# DIY_OpenEVSE_PLUS_v2w.net
KiCad netlist of a schematic drawn in EAGLE
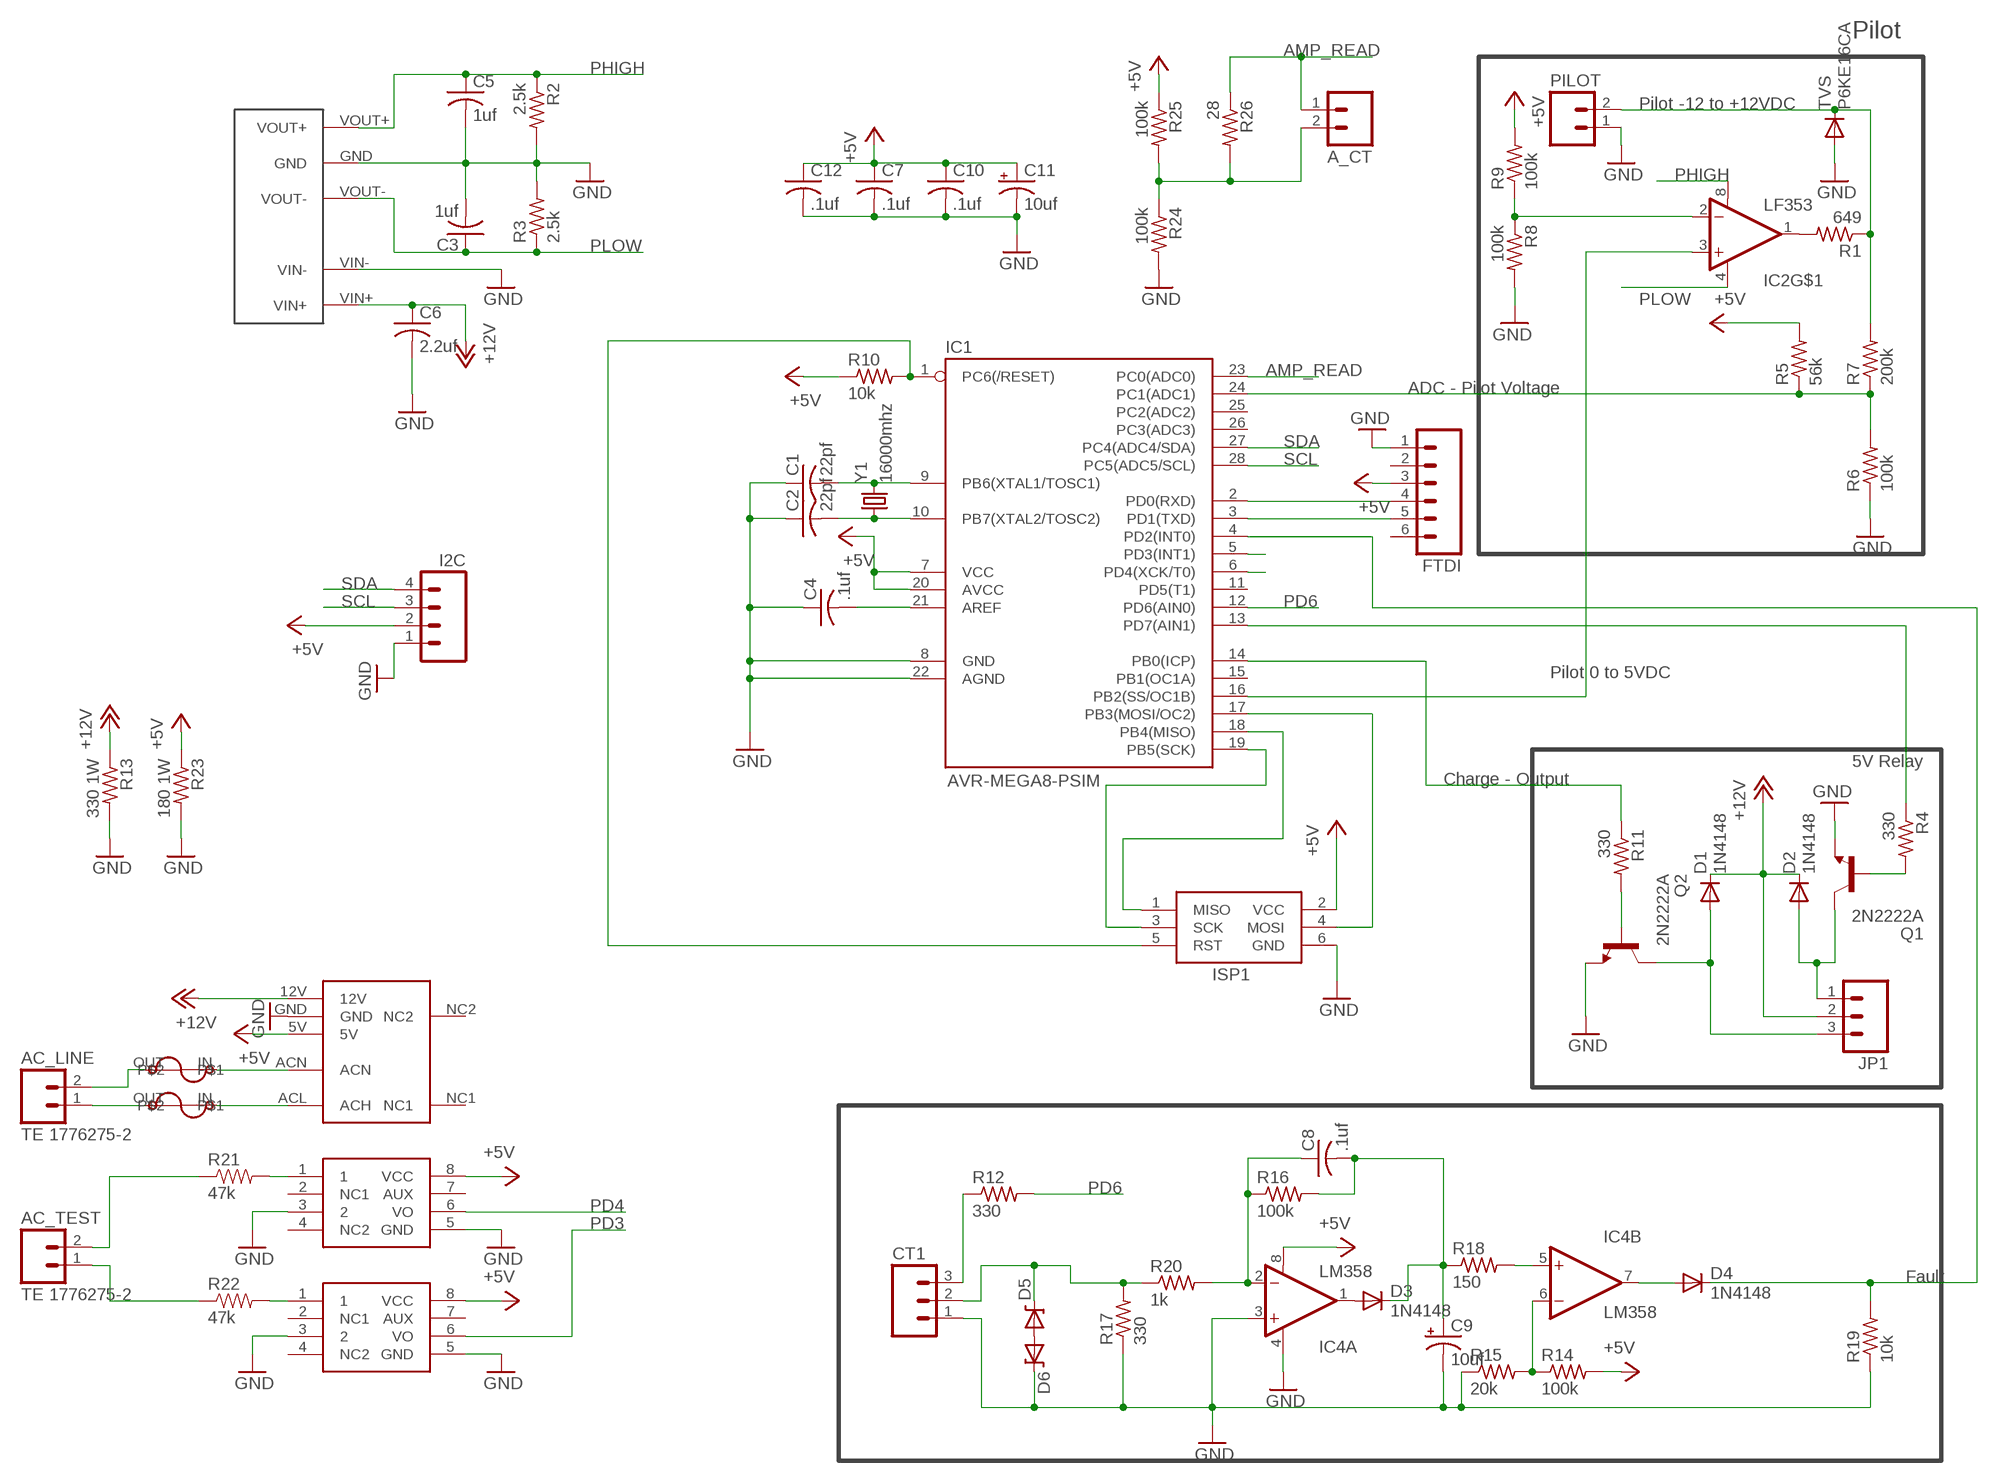
[diagram p0: schematic, sheet 1]

(export (version "E")
  (design (tool "Eeschema 10.0.6"))
  (components
    (comp (ref "AC_LINE")
      (value "TE 1776275-2")
      (footprint "eagle-import:SCREWTERMINAL-3.5MM-2_LOCK")
      (libsource (lib "eagle-import") (part "M023.5MM_LOCK"))
    )
    (comp (ref "AC_TEST")
      (value "TE 1776275-2")
      (footprint "eagle-import:SCREWTERMINAL-3.5MM-2_LOCK")
      (libsource (lib "eagle-import") (part "M023.5MM_LOCK"))
    )
    (comp (ref "A_CT")
      (value "M02PTH")
      (footprint "eagle-import:1X02")
      (libsource (lib "eagle-import") (part "M02PTH"))
    )
    (comp (ref "C1")
      (value "22pf")
      (footprint "eagle-import:C025-024X044")
      (libsource (lib "eagle-import") (part "C-US025-024X044"))
    )
    (comp (ref "C2")
      (value "22pf")
      (footprint "eagle-import:C025-024X044")
      (libsource (lib "eagle-import") (part "C-US025-024X044"))
    )
    (comp (ref "C3")
      (value "1uf")
      (footprint "eagle-import:C025-024X044")
      (libsource (lib "eagle-import") (part "C-US025-024X044"))
    )
    (comp (ref "C4")
      (value ".1uf")
      (footprint "eagle-import:C025-024X044")
      (libsource (lib "eagle-import") (part "C-US025-024X044"))
    )
    (comp (ref "C5")
      (value "1uf")
      (footprint "eagle-import:C025-024X044")
      (libsource (lib "eagle-import") (part "C-US025-024X044"))
    )
    (comp (ref "C6")
      (value "2.2uf")
      (footprint "eagle-import:C025-024X044")
      (libsource (lib "eagle-import") (part "C-US025-024X044"))
    )
    (comp (ref "C7")
      (value ".1uf")
      (footprint "eagle-import:C025-024X044")
      (libsource (lib "eagle-import") (part "C-US025-024X044"))
    )
    (comp (ref "C8")
      (value ".1uf")
      (footprint "eagle-import:C025-024X044")
      (libsource (lib "eagle-import") (part "C-US025-024X044"))
    )
    (comp (ref "C9")
      (value "10uf")
      (footprint "eagle-import:CPOL-RADIAL-10UF-25V")
      (libsource (lib "eagle-import") (part "CAP_POLPTH2"))
    )
    (comp (ref "C10")
      (value ".1uf")
      (footprint "eagle-import:C025-024X044")
      (libsource (lib "eagle-import") (part "C-US025-024X044"))
    )
    (comp (ref "C11")
      (value "10uf")
      (footprint "eagle-import:CPOL-RADIAL-10UF-25V")
      (libsource (lib "eagle-import") (part "CAP_POLPTH2"))
    )
    (comp (ref "C12")
      (value ".1uf")
      (footprint "eagle-import:C025-024X044")
      (libsource (lib "eagle-import") (part "C-US025-024X044"))
    )
    (comp (ref "CT1")
      (value "M03LOCK")
      (footprint "eagle-import:1X03_LOCK")
      (libsource (lib "eagle-import") (part "M03LOCK"))
    )
    (comp (ref "D1")
      (value "1N4148")
      (footprint "eagle-import:DIODE-1N4148")
      (libsource (lib "eagle-import") (part "DIODE1N4148"))
    )
    (comp (ref "D2")
      (value "1N4148")
      (footprint "eagle-import:DIODE-1N4148")
      (libsource (lib "eagle-import") (part "DIODE1N4148"))
    )
    (comp (ref "D3")
      (value "1N4148")
      (footprint "eagle-import:DIODE-1N4148")
      (libsource (lib "eagle-import") (part "DIODE1N4148"))
    )
    (comp (ref "D4")
      (value "1N4148")
      (footprint "eagle-import:DIODE-1N4148")
      (libsource (lib "eagle-import") (part "DIODE1N4148"))
    )
    (comp (ref "D5")
      (value "DIODE-ZENERPTH")
      (footprint "eagle-import:DIODE-ZENER")
      (libsource (lib "eagle-import") (part "DIODE-ZENERPTH"))
    )
    (comp (ref "D6")
      (value "DIODE-ZENERPTH")
      (footprint "eagle-import:DIODE-ZENER")
      (libsource (lib "eagle-import") (part "DIODE-ZENERPTH"))
    )
    (comp (ref "DCDC")
      (value "D107E")
      (footprint "eagle-import:DCDC_SIP")
      (libsource (lib "eagle-import") (part "DCDC_SIP"))
    )
    (comp (ref "FTDI")
      (value "M06LOCK")
      (footprint "eagle-import:1X06_LOCK")
      (libsource (lib "eagle-import") (part "M06LOCK"))
    )
    (comp (ref "I2C")
      (value "M04LOCK")
      (footprint "eagle-import:1X04_LOCK")
      (libsource (lib "eagle-import") (part "M04LOCK"))
    )
    (comp (ref "IC1")
      (value "AVR-MEGA8-PSIM")
      (footprint "eagle-import:DIL28-3-SIMON")
      (libsource (lib "eagle-import") (part "AVR-MEGA8-PSIM"))
    )
    (comp (ref "IC2")
      (value "LF353")
      (footprint "eagle-import:DIP08")
      (libsource (lib "eagle-import") (part "LM358"))
    )
    (comp (ref "IC3")
      (value "MID400")
      (footprint "eagle-import:DIP08")
      (libsource (lib "eagle-import") (part "MID400"))
    )
    (comp (ref "IC4")
      (value "LM358")
      (footprint "eagle-import:DIP08")
      (libsource (lib "eagle-import") (part "OPAMP-DUALDIP"))
    )
    (comp (ref "IC5")
      (value "MID400")
      (footprint "eagle-import:DIP08")
      (libsource (lib "eagle-import") (part "MID400"))
    )
    (comp (ref "ISP1")
      (value "AVRISP-6")
      (footprint "eagle-import:AVRISP")
      (libsource (lib "eagle-import") (part "AVRISP-6"))
    )
    (comp (ref "JP1")
      (value "M03SCREW_LOCK")
      (footprint "eagle-import:SCREWTERMINAL-3.5MM-3_LOCK.007S")
      (libsource (lib "eagle-import") (part "M03SCREW_LOCK"))
    )
    (comp (ref "PILOT")
      (value "M025MM")
      (footprint "eagle-import:SCREWTERMINAL-5MM-2")
      (libsource (lib "eagle-import") (part "M025MM"))
    )
    (comp (ref "Q1")
      (value "2N2222A")
      (footprint "eagle-import:TO18")
      (libsource (lib "eagle-import") (part "2N2222A"))
    )
    (comp (ref "Q2")
      (value "2N2222A")
      (footprint "eagle-import:TO18")
      (libsource (lib "eagle-import") (part "2N2222A"))
    )
    (comp (ref "R1")
      (value "649")
      (footprint "eagle-import:0309V")
      (libsource (lib "eagle-import") (part "R-US_0309/V"))
    )
    (comp (ref "R2")
      (value "2.5k")
      (footprint "eagle-import:0309V")
      (libsource (lib "eagle-import") (part "R-US_0309/V"))
    )
    (comp (ref "R3")
      (value "2.5k")
      (footprint "eagle-import:0309V")
      (libsource (lib "eagle-import") (part "R-US_0309/V"))
    )
    (comp (ref "R4")
      (value "330")
      (footprint "eagle-import:0309V")
      (libsource (lib "eagle-import") (part "R-US_0309/V"))
    )
    (comp (ref "R5")
      (value "56k")
      (footprint "eagle-import:0309V")
      (libsource (lib "eagle-import") (part "R-US_0309/V"))
    )
    (comp (ref "R6")
      (value "100k")
      (footprint "eagle-import:0309V")
      (libsource (lib "eagle-import") (part "R-US_0309/V"))
    )
    (comp (ref "R7")
      (value "200k")
      (footprint "eagle-import:0309V")
      (libsource (lib "eagle-import") (part "R-US_0309/V"))
    )
    (comp (ref "R8")
      (value "100k")
      (footprint "eagle-import:0309V")
      (libsource (lib "eagle-import") (part "R-US_0309/V"))
    )
    (comp (ref "R9")
      (value "100k")
      (footprint "eagle-import:0309V")
      (libsource (lib "eagle-import") (part "R-US_0309/V"))
    )
    (comp (ref "R10")
      (value "10k")
      (footprint "eagle-import:0309V")
      (libsource (lib "eagle-import") (part "R-US_0309/V"))
    )
    (comp (ref "R11")
      (value "330")
      (footprint "eagle-import:0309V")
      (libsource (lib "eagle-import") (part "R-US_0309/V"))
    )
    (comp (ref "R12")
      (value "330")
      (footprint "eagle-import:0309V")
      (libsource (lib "eagle-import") (part "R-US_0309/V"))
    )
    (comp (ref "R13")
      (value "330 1W")
      (footprint "eagle-import:0309V")
      (libsource (lib "eagle-import") (part "R-US_0309/V"))
    )
    (comp (ref "R14")
      (value "100k")
      (footprint "eagle-import:0309V")
      (libsource (lib "eagle-import") (part "R-US_0309/V"))
    )
    (comp (ref "R15")
      (value "20k")
      (footprint "eagle-import:0309V")
      (libsource (lib "eagle-import") (part "R-US_0309/V"))
    )
    (comp (ref "R16")
      (value "100k")
      (footprint "eagle-import:0309V")
      (libsource (lib "eagle-import") (part "R-US_0309/V"))
    )
    (comp (ref "R17")
      (value "330")
      (footprint "eagle-import:0309V")
      (libsource (lib "eagle-import") (part "R-US_0309/V"))
    )
    (comp (ref "R18")
      (value "150")
      (footprint "eagle-import:0309V")
      (libsource (lib "eagle-import") (part "R-US_0309/V"))
    )
    (comp (ref "R19")
      (value "10k")
      (footprint "eagle-import:0309V")
      (libsource (lib "eagle-import") (part "R-US_0309/V"))
    )
    (comp (ref "R20")
      (value "1k")
      (footprint "eagle-import:0309V")
      (libsource (lib "eagle-import") (part "R-US_0309/V"))
    )
    (comp (ref "R21")
      (value "47k")
      (footprint "eagle-import:AXIAL-0.4")
      (libsource (lib "eagle-import") (part "RESISTORPTH-1/4W"))
    )
    (comp (ref "R22")
      (value "47k")
      (footprint "eagle-import:AXIAL-0.4")
      (libsource (lib "eagle-import") (part "RESISTORPTH-1/4W"))
    )
    (comp (ref "R23")
      (value "180 1W")
      (footprint "eagle-import:0309V")
      (libsource (lib "eagle-import") (part "R-US_0309/V"))
    )
    (comp (ref "R24")
      (value "100k")
      (footprint "eagle-import:0309V")
      (libsource (lib "eagle-import") (part "rcl_R-US_0309/V"))
    )
    (comp (ref "R25")
      (value "100k")
      (footprint "eagle-import:0309V")
      (libsource (lib "eagle-import") (part "rcl_R-US_0309/V"))
    )
    (comp (ref "R26")
      (value "28")
      (footprint "eagle-import:0309V")
      (libsource (lib "eagle-import") (part "rcl_R-US_0309/V"))
    )
    (comp (ref "TVS")
      (value "P6KE16CA")
      (footprint "eagle-import:DIODE-1N4001")
      (libsource (lib "eagle-import") (part "DIODEPTH"))
    )
    (comp (ref "U$3")
      (value "BEL1AFUSE")
      (footprint "eagle-import:BELFUSE1A")
      (libsource (lib "eagle-import") (part "BEL1AFUSE"))
    )
    (comp (ref "U$4")
      (value "MPM-04E-1205")
      (footprint "eagle-import:MPM-04E-1205")
      (libsource (lib "eagle-import") (part "MPM-04E-1205"))
    )
    (comp (ref "U$5")
      (value "BEL1AFUSE")
      (footprint "eagle-import:BELFUSE1A")
      (libsource (lib "eagle-import") (part "BEL1AFUSE"))
    )
    (comp (ref "Y1")
      (value "16000mhz")
      (footprint "eagle-import:HC49U-V")
      (libsource (lib "eagle-import") (part "CRYSTALHC49UV"))
    )
  )
  (nets
    (net (code "1") (name "+5V") (class "Default")
      (node (ref "C10") (pin "1") (pinfunction "1_1") (pintype "passive"))
      (node (ref "C11") (pin "1") (pinfunction "+_1") (pintype "passive"))
      (node (ref "C12") (pin "1") (pinfunction "1_1") (pintype "passive"))
      (node (ref "C7") (pin "1") (pinfunction "1_1") (pintype "passive"))
      (node (ref "FTDI") (pin "3") (pinfunction "3_3") (pintype "passive"))
      (node (ref "I2C") (pin "2") (pinfunction "2_2") (pintype "passive"))
      (node (ref "IC1") (pin "20") (pinfunction "AVCC_20") (pintype "bidirectional"))
      (node (ref "IC1") (pin "7") (pinfunction "VCC_7") (pintype "bidirectional"))
      (node (ref "IC3") (pin "8") (pinfunction "VCC_8") (pintype "bidirectional"))
      (node (ref "IC4") (pin "8") (pinfunction "V+_8") (pintype "power_in"))
      (node (ref "IC5") (pin "8") (pinfunction "VCC_8") (pintype "bidirectional"))
      (node (ref "ISP1") (pin "2") (pinfunction "VCC_2") (pintype "power_in"))
      (node (ref "R10") (pin "1") (pinfunction "1_1") (pintype "passive"))
      (node (ref "R14") (pin "2") (pinfunction "2_2") (pintype "passive"))
      (node (ref "R23") (pin "1") (pinfunction "1_1") (pintype "passive"))
      (node (ref "R25") (pin "1") (pinfunction "1_1") (pintype "passive"))
      (node (ref "R5") (pin "2") (pinfunction "2_2") (pintype "passive"))
      (node (ref "R9") (pin "2") (pinfunction "2_2") (pintype "passive"))
      (node (ref "U$4") (pin "5V") (pinfunction "5V_5V") (pintype "bidirectional"))
    )
    (net (code "2") (name "+12V") (class "Default")
      (node (ref "C6") (pin "1") (pinfunction "1_1") (pintype "passive"))
      (node (ref "D1") (pin "C") (pinfunction "C_C") (pintype "passive"))
      (node (ref "D2") (pin "C") (pinfunction "C_C") (pintype "passive"))
      (node (ref "DCDC") (pin "VIN+") (pinfunction "VIN+_VIN+") (pintype "bidirectional"))
      (node (ref "JP1") (pin "2") (pinfunction "2_2") (pintype "passive"))
      (node (ref "R13") (pin "1") (pinfunction "1_1") (pintype "passive"))
      (node (ref "U$4") (pin "12V") (pinfunction "12V_12V") (pintype "bidirectional"))
    )
    (net (code "3") (name "/AMP_READ") (class "Default")
      (node (ref "A_CT") (pin "1") (pinfunction "1_1") (pintype "passive"))
      (node (ref "IC1") (pin "23") (pinfunction "PC0(ADC0)_23") (pintype "bidirectional"))
      (node (ref "R26") (pin "1") (pinfunction "1_1") (pintype "passive"))
    )
    (net (code "4") (name "/PD3") (class "Default")
      (node (ref "IC1") (pin "5") (pinfunction "PD3(INT1)_5") (pintype "bidirectional"))
      (node (ref "IC5") (pin "6") (pinfunction "VO_6") (pintype "bidirectional"))
    )
    (net (code "5") (name "/PD4") (class "Default")
      (node (ref "IC1") (pin "6") (pinfunction "PD4(XCK/T0)_6") (pintype "bidirectional"))
      (node (ref "IC3") (pin "6") (pinfunction "VO_6") (pintype "bidirectional"))
    )
    (net (code "6") (name "/PD6") (class "Default")
      (node (ref "IC1") (pin "12") (pinfunction "PD6(AIN0)_12") (pintype "bidirectional"))
      (node (ref "R12") (pin "2") (pinfunction "2_2") (pintype "passive"))
    )
    (net (code "7") (name "/PHIGH") (class "Default")
      (node (ref "C5") (pin "1") (pinfunction "1_1") (pintype "passive"))
      (node (ref "DCDC") (pin "VOUT+") (pinfunction "VOUT+_VOUT+") (pintype "bidirectional"))
      (node (ref "IC2") (pin "8") (pinfunction "V+_8") (pintype "power_in"))
      (node (ref "R2") (pin "1") (pinfunction "1_1") (pintype "passive"))
    )
    (net (code "8") (name "/PLOW") (class "Default")
      (node (ref "C3") (pin "1") (pinfunction "1_1") (pintype "passive"))
      (node (ref "DCDC") (pin "VOUT-") (pinfunction "VOUT-_VOUT-") (pintype "bidirectional"))
      (node (ref "IC2") (pin "4") (pinfunction "V-_4") (pintype "power_in"))
      (node (ref "R3") (pin "1") (pinfunction "1_1") (pintype "passive"))
    )
    (net (code "9") (name "/SCL") (class "Default")
      (node (ref "I2C") (pin "3") (pinfunction "3_3") (pintype "passive"))
      (node (ref "IC1") (pin "28") (pinfunction "PC5(ADC5/SCL)_28") (pintype "bidirectional"))
    )
    (net (code "10") (name "/SDA") (class "Default")
      (node (ref "I2C") (pin "4") (pinfunction "4_4") (pintype "passive"))
      (node (ref "IC1") (pin "27") (pinfunction "PC4(ADC4/SDA)_27") (pintype "bidirectional"))
    )
    (net (code "11") (name "GND") (class "Default")
      (node (ref "C1") (pin "1") (pinfunction "1_1") (pintype "passive"))
      (node (ref "C10") (pin "2") (pinfunction "2_2") (pintype "passive"))
      (node (ref "C11") (pin "2") (pinfunction "-_2") (pintype "passive"))
      (node (ref "C12") (pin "2") (pinfunction "2_2") (pintype "passive"))
      (node (ref "C2") (pin "1") (pinfunction "1_1") (pintype "passive"))
      (node (ref "C3") (pin "2") (pinfunction "2_2") (pintype "passive"))
      (node (ref "C4") (pin "1") (pinfunction "1_1") (pintype "passive"))
      (node (ref "C5") (pin "2") (pinfunction "2_2") (pintype "passive"))
      (node (ref "C6") (pin "2") (pinfunction "2_2") (pintype "passive"))
      (node (ref "C7") (pin "2") (pinfunction "2_2") (pintype "passive"))
      (node (ref "C9") (pin "2") (pinfunction "-_2") (pintype "passive"))
      (node (ref "CT1") (pin "1") (pinfunction "1_1") (pintype "passive"))
      (node (ref "D6") (pin "P$1") (pinfunction "C_P$1") (pintype "passive"))
      (node (ref "DCDC") (pin "GND") (pinfunction "GND_GND") (pintype "bidirectional"))
      (node (ref "DCDC") (pin "VIN-") (pinfunction "VIN-_VIN-") (pintype "bidirectional"))
      (node (ref "FTDI") (pin "1") (pinfunction "1_1") (pintype "passive"))
      (node (ref "I2C") (pin "1") (pinfunction "1_1") (pintype "passive"))
      (node (ref "IC1") (pin "22") (pinfunction "AGND_22") (pintype "bidirectional"))
      (node (ref "IC1") (pin "8") (pinfunction "GND_8") (pintype "bidirectional"))
      (node (ref "IC3") (pin "3") (pinfunction "2_3") (pintype "bidirectional"))
      (node (ref "IC3") (pin "5") (pinfunction "GND_5") (pintype "bidirectional"))
      (node (ref "IC4") (pin "3") (pinfunction "+IN_3") (pintype "input"))
      (node (ref "IC4") (pin "4") (pinfunction "V-_4") (pintype "power_in"))
      (node (ref "IC5") (pin "3") (pinfunction "2_3") (pintype "bidirectional"))
      (node (ref "IC5") (pin "5") (pinfunction "GND_5") (pintype "bidirectional"))
      (node (ref "ISP1") (pin "6") (pinfunction "GND_6") (pintype "power_in"))
      (node (ref "PILOT") (pin "1") (pinfunction "1_1") (pintype "passive"))
      (node (ref "Q1") (pin "1") (pinfunction "E_1") (pintype "passive"))
      (node (ref "Q2") (pin "1") (pinfunction "E_1") (pintype "passive"))
      (node (ref "R13") (pin "2") (pinfunction "2_2") (pintype "passive"))
      (node (ref "R15") (pin "1") (pinfunction "1_1") (pintype "passive"))
      (node (ref "R17") (pin "1") (pinfunction "1_1") (pintype "passive"))
      (node (ref "R19") (pin "1") (pinfunction "1_1") (pintype "passive"))
      (node (ref "R2") (pin "2") (pinfunction "2_2") (pintype "passive"))
      (node (ref "R23") (pin "2") (pinfunction "2_2") (pintype "passive"))
      (node (ref "R24") (pin "2") (pinfunction "2_2") (pintype "passive"))
      (node (ref "R3") (pin "2") (pinfunction "2_2") (pintype "passive"))
      (node (ref "R6") (pin "1") (pinfunction "1_1") (pintype "passive"))
      (node (ref "R8") (pin "2") (pinfunction "2_2") (pintype "passive"))
      (node (ref "TVS") (pin "A") (pinfunction "A_A") (pintype "passive"))
      (node (ref "U$4") (pin "GND") (pinfunction "GND_GND") (pintype "bidirectional"))
    )
    (net (code "12") (name "Net-(A_CT-Pad2)") (class "Default")
      (node (ref "A_CT") (pin "2") (pinfunction "2_2") (pintype "passive"))
      (node (ref "R24") (pin "1") (pinfunction "1_1") (pintype "passive"))
      (node (ref "R25") (pin "2") (pinfunction "2_2") (pintype "passive"))
      (node (ref "R26") (pin "2") (pinfunction "2_2") (pintype "passive"))
    )
    (net (code "13") (name "Net-(C9-+)") (class "Default")
      (node (ref "C8") (pin "2") (pinfunction "2_2") (pintype "passive"))
      (node (ref "C9") (pin "1") (pinfunction "+_1") (pintype "passive"))
      (node (ref "D3") (pin "C") (pinfunction "C_C") (pintype "passive"))
      (node (ref "R16") (pin "2") (pinfunction "2_2") (pintype "passive"))
      (node (ref "R18") (pin "1") (pinfunction "1_1") (pintype "passive"))
    )
    (net (code "14") (name "Net-(CT1-Pad3)") (class "Default")
      (node (ref "CT1") (pin "3") (pinfunction "3_3") (pintype "passive"))
      (node (ref "R12") (pin "1") (pinfunction "1_1") (pintype "passive"))
    )
    (net (code "15") (name "Net-(D5-A)") (class "Default")
      (node (ref "D5") (pin "P$2") (pinfunction "A_P$2") (pintype "passive"))
      (node (ref "D6") (pin "P$2") (pinfunction "A_P$2") (pintype "passive"))
    )
    (net (code "16") (name "Net-(D5-C)") (class "Default")
      (node (ref "CT1") (pin "2") (pinfunction "2_2") (pintype "passive"))
      (node (ref "D5") (pin "P$1") (pinfunction "C_P$1") (pintype "passive"))
      (node (ref "R17") (pin "2") (pinfunction "2_2") (pintype "passive"))
      (node (ref "R20") (pin "1") (pinfunction "1_1") (pintype "passive"))
    )
    (net (code "17") (name "Net-(IC1-AREF)") (class "Default")
      (node (ref "C4") (pin "2") (pinfunction "2_2") (pintype "passive"))
      (node (ref "IC1") (pin "21") (pinfunction "AREF_21") (pintype "bidirectional"))
    )
    (net (code "18") (name "Net-(IC1-PB0(ICP))") (class "Default")
      (node (ref "IC1") (pin "14") (pinfunction "PB0(ICP)_14") (pintype "bidirectional"))
      (node (ref "R11") (pin "1") (pinfunction "1_1") (pintype "passive"))
    )
    (net (code "19") (name "Net-(IC1-PB2(SS{slash}OC1B))") (class "Default")
      (node (ref "IC1") (pin "16") (pinfunction "PB2(SS/OC1B)_16") (pintype "bidirectional"))
      (node (ref "IC2") (pin "3") (pinfunction "+IN_3") (pintype "input"))
    )
    (net (code "20") (name "Net-(IC1-PB3(MOSI{slash}OC2))") (class "Default")
      (node (ref "IC1") (pin "17") (pinfunction "PB3(MOSI/OC2)_17") (pintype "bidirectional"))
      (node (ref "ISP1") (pin "4") (pinfunction "MOSI_4") (pintype "output"))
    )
    (net (code "21") (name "Net-(IC1-PB4(MISO))") (class "Default")
      (node (ref "IC1") (pin "18") (pinfunction "PB4(MISO)_18") (pintype "bidirectional"))
      (node (ref "ISP1") (pin "1") (pinfunction "MISO_1") (pintype "input"))
    )
    (net (code "22") (name "Net-(IC1-PB5(SCK))") (class "Default")
      (node (ref "IC1") (pin "19") (pinfunction "PB5(SCK)_19") (pintype "bidirectional"))
      (node (ref "ISP1") (pin "3") (pinfunction "SCK_3") (pintype "output"))
    )
    (net (code "23") (name "Net-(IC1-PB6(XTAL1{slash}TOSC1))") (class "Default")
      (node (ref "C1") (pin "2") (pinfunction "2_2") (pintype "passive"))
      (node (ref "IC1") (pin "9") (pinfunction "PB6(XTAL1/TOSC1)_9") (pintype "bidirectional"))
      (node (ref "Y1") (pin "2") (pinfunction "2_2") (pintype "passive"))
    )
    (net (code "24") (name "Net-(IC1-PB7(XTAL2{slash}TOSC2))") (class "Default")
      (node (ref "C2") (pin "2") (pinfunction "2_2") (pintype "passive"))
      (node (ref "IC1") (pin "10") (pinfunction "PB7(XTAL2/TOSC2)_10") (pintype "bidirectional"))
      (node (ref "Y1") (pin "1") (pinfunction "1_1") (pintype "passive"))
    )
    (net (code "25") (name "Net-(IC1-PC1(ADC1))") (class "Default")
      (node (ref "IC1") (pin "24") (pinfunction "PC1(ADC1)_24") (pintype "bidirectional"))
      (node (ref "R5") (pin "1") (pinfunction "1_1") (pintype "passive"))
      (node (ref "R6") (pin "2") (pinfunction "2_2") (pintype "passive"))
      (node (ref "R7") (pin "1") (pinfunction "1_1") (pintype "passive"))
    )
    (net (code "26") (name "Net-(IC1-PC6({slash}RESET))") (class "Default")
      (node (ref "IC1") (pin "1") (pinfunction "PC6(/RESET)_1") (pintype "bidirectional"))
      (node (ref "ISP1") (pin "5") (pinfunction "RST_5") (pintype "output"))
      (node (ref "R10") (pin "2") (pinfunction "2_2") (pintype "passive"))
    )
    (net (code "27") (name "Net-(IC1-PD0(RXD))") (class "Default")
      (node (ref "FTDI") (pin "4") (pinfunction "4_4") (pintype "passive"))
      (node (ref "IC1") (pin "2") (pinfunction "PD0(RXD)_2") (pintype "bidirectional"))
    )
    (net (code "28") (name "Net-(IC1-PD1(TXD))") (class "Default")
      (node (ref "FTDI") (pin "5") (pinfunction "5_5") (pintype "passive"))
      (node (ref "IC1") (pin "3") (pinfunction "PD1(TXD)_3") (pintype "bidirectional"))
    )
    (net (code "29") (name "Net-(IC1-PD2(INT0))") (class "Default")
      (node (ref "D4") (pin "C") (pinfunction "C_C") (pintype "passive"))
      (node (ref "IC1") (pin "4") (pinfunction "PD2(INT0)_4") (pintype "bidirectional"))
      (node (ref "R19") (pin "2") (pinfunction "2_2") (pintype "passive"))
    )
    (net (code "30") (name "Net-(IC1-PD7(AIN1))") (class "Default")
      (node (ref "IC1") (pin "13") (pinfunction "PD7(AIN1)_13") (pintype "bidirectional"))
      (node (ref "R4") (pin "1") (pinfunction "1_1") (pintype "passive"))
    )
    (net (code "31") (name "Net-(IC2A--IN)") (class "Default")
      (node (ref "IC2") (pin "2") (pinfunction "-IN_2") (pintype "input"))
      (node (ref "R8") (pin "1") (pinfunction "1_1") (pintype "passive"))
      (node (ref "R9") (pin "1") (pinfunction "1_1") (pintype "passive"))
    )
    (net (code "32") (name "Net-(IC2A-OUT)") (class "Default")
      (node (ref "IC2") (pin "1") (pinfunction "OUT_1") (pintype "output"))
      (node (ref "R1") (pin "2") (pinfunction "2_2") (pintype "passive"))
    )
    (net (code "33") (name "Net-(IC4A--IN)") (class "Default")
      (node (ref "C8") (pin "1") (pinfunction "1_1") (pintype "passive"))
      (node (ref "IC4") (pin "2") (pinfunction "-IN_2") (pintype "input"))
      (node (ref "R16") (pin "1") (pinfunction "1_1") (pintype "passive"))
      (node (ref "R20") (pin "2") (pinfunction "2_2") (pintype "passive"))
    )
    (net (code "34") (name "Net-(IC4A-OUT)") (class "Default")
      (node (ref "D3") (pin "A") (pinfunction "A_A") (pintype "passive"))
      (node (ref "IC4") (pin "1") (pinfunction "OUT_1") (pintype "output"))
    )
    (net (code "35") (name "Net-(IC4B-+IN)") (class "Default")
      (node (ref "IC4") (pin "5") (pinfunction "+IN_5") (pintype "input"))
      (node (ref "R18") (pin "2") (pinfunction "2_2") (pintype "passive"))
    )
    (net (code "36") (name "Net-(IC4B--IN)") (class "Default")
      (node (ref "IC4") (pin "6") (pinfunction "-IN_6") (pintype "input"))
      (node (ref "R14") (pin "1") (pinfunction "1_1") (pintype "passive"))
      (node (ref "R15") (pin "2") (pinfunction "2_2") (pintype "passive"))
    )
    (net (code "37") (name "Net-(IC4B-OUT)") (class "Default")
      (node (ref "D4") (pin "A") (pinfunction "A_A") (pintype "passive"))
      (node (ref "IC4") (pin "7") (pinfunction "OUT_7") (pintype "output"))
    )
    (net (code "38") (name "Net-(PILOT-Pad2)") (class "Default")
      (node (ref "PILOT") (pin "2") (pinfunction "2_2") (pintype "passive"))
      (node (ref "R1") (pin "1") (pinfunction "1_1") (pintype "passive"))
      (node (ref "R7") (pin "2") (pinfunction "2_2") (pintype "passive"))
      (node (ref "TVS") (pin "C") (pinfunction "C_C") (pintype "passive"))
    )
    (net (code "39") (name "Net-(Q1-B)") (class "Default")
      (node (ref "Q1") (pin "2") (pinfunction "B_2") (pintype "passive"))
      (node (ref "R4") (pin "2") (pinfunction "2_2") (pintype "passive"))
    )
    (net (code "40") (name "Net-(Q1-C)") (class "Default")
      (node (ref "D2") (pin "A") (pinfunction "A_A") (pintype "passive"))
      (node (ref "JP1") (pin "1") (pinfunction "1_1") (pintype "passive"))
      (node (ref "Q1") (pin "3") (pinfunction "C_3") (pintype "passive"))
    )
    (net (code "41") (name "Net-(Q2-B)") (class "Default")
      (node (ref "Q2") (pin "2") (pinfunction "B_2") (pintype "passive"))
      (node (ref "R11") (pin "2") (pinfunction "2_2") (pintype "passive"))
    )
    (net (code "42") (name "Net-(Q2-C)") (class "Default")
      (node (ref "D1") (pin "A") (pinfunction "A_A") (pintype "passive"))
      (node (ref "JP1") (pin "3") (pinfunction "3_3") (pintype "passive"))
      (node (ref "Q2") (pin "3") (pinfunction "C_3") (pintype "passive"))
    )
    (net (code "43") (name "Net-(R21-1)") (class "Default")
      (node (ref "AC_TEST") (pin "2") (pinfunction "2_2") (pintype "passive"))
      (node (ref "R21") (pin "P$1") (pinfunction "1_P$1") (pintype "passive"))
    )
    (net (code "44") (name "Net-(R21-2)") (class "Default")
      (node (ref "IC3") (pin "1") (pinfunction "1_1") (pintype "bidirectional"))
      (node (ref "R21") (pin "P$2") (pinfunction "2_P$2") (pintype "passive"))
    )
    (net (code "45") (name "Net-(R22-1)") (class "Default")
      (node (ref "AC_TEST") (pin "1") (pinfunction "1_1") (pintype "passive"))
      (node (ref "R22") (pin "P$1") (pinfunction "1_P$1") (pintype "passive"))
    )
    (net (code "46") (name "Net-(R22-2)") (class "Default")
      (node (ref "IC5") (pin "1") (pinfunction "1_1") (pintype "bidirectional"))
      (node (ref "R22") (pin "P$2") (pinfunction "2_P$2") (pintype "passive"))
    )
    (net (code "47") (name "Net-(U$3-P$1)") (class "Default")
      (node (ref "AC_LINE") (pin "1") (pinfunction "1_1") (pintype "passive"))
      (node (ref "U$3") (pin "OUT") (pinfunction "P$1_OUT") (pintype "bidirectional"))
    )
    (net (code "48") (name "Net-(U$3-P$2)") (class "Default")
      (node (ref "U$3") (pin "IN") (pinfunction "P$2_IN") (pintype "bidirectional"))
      (node (ref "U$4") (pin "ACL") (pinfunction "ACH_ACL") (pintype "bidirectional"))
    )
    (net (code "49") (name "Net-(U$5-P$1)") (class "Default")
      (node (ref "AC_LINE") (pin "2") (pinfunction "2_2") (pintype "passive"))
      (node (ref "U$5") (pin "OUT") (pinfunction "P$1_OUT") (pintype "bidirectional"))
    )
    (net (code "50") (name "Net-(U$5-P$2)") (class "Default")
      (node (ref "U$4") (pin "ACN") (pinfunction "ACN_ACN") (pintype "bidirectional"))
      (node (ref "U$5") (pin "IN") (pinfunction "P$2_IN") (pintype "bidirectional"))
    )
    (net (code "51") (name "unconnected-(FTDI-Pad2)") (class "Default")
      (node (ref "FTDI") (pin "2") (pinfunction "2_2") (pintype "passive"))
    )
    (net (code "52") (name "unconnected-(FTDI-Pad6)") (class "Default")
      (node (ref "FTDI") (pin "6") (pinfunction "6_6") (pintype "passive"))
    )
    (net (code "53") (name "unconnected-(IC1-PB1(OC1A)-Pad15)") (class "Default")
      (node (ref "IC1") (pin "15") (pinfunction "PB1(OC1A)_15") (pintype "bidirectional"))
    )
    (net (code "54") (name "unconnected-(IC1-PC2(ADC2)-Pad25)") (class "Default")
      (node (ref "IC1") (pin "25") (pinfunction "PC2(ADC2)_25") (pintype "bidirectional"))
    )
    (net (code "55") (name "unconnected-(IC1-PC3(ADC3)-Pad26)") (class "Default")
      (node (ref "IC1") (pin "26") (pinfunction "PC3(ADC3)_26") (pintype "bidirectional"))
    )
    (net (code "56") (name "unconnected-(IC1-PD5(T1)-Pad11)") (class "Default")
      (node (ref "IC1") (pin "11") (pinfunction "PD5(T1)_11") (pintype "bidirectional"))
    )
    (net (code "57") (name "unconnected-(IC3-AUX-Pad7)") (class "Default")
      (node (ref "IC3") (pin "7") (pinfunction "AUX_7") (pintype "bidirectional"))
    )
    (net (code "58") (name "unconnected-(IC3-NC1-Pad2)") (class "Default")
      (node (ref "IC3") (pin "2") (pinfunction "NC1_2") (pintype "bidirectional"))
    )
    (net (code "59") (name "unconnected-(IC3-NC2-Pad4)") (class "Default")
      (node (ref "IC3") (pin "4") (pinfunction "NC2_4") (pintype "bidirectional"))
    )
    (net (code "60") (name "unconnected-(IC5-AUX-Pad7)") (class "Default")
      (node (ref "IC5") (pin "7") (pinfunction "AUX_7") (pintype "bidirectional"))
    )
    (net (code "61") (name "unconnected-(IC5-NC1-Pad2)") (class "Default")
      (node (ref "IC5") (pin "2") (pinfunction "NC1_2") (pintype "bidirectional"))
    )
    (net (code "62") (name "unconnected-(IC5-NC2-Pad4)") (class "Default")
      (node (ref "IC5") (pin "4") (pinfunction "NC2_4") (pintype "bidirectional"))
    )
    (net (code "63") (name "unconnected-(U$4-PadNC1)") (class "Default")
      (node (ref "U$4") (pin "NC1") (pinfunction "NC1_NC1") (pintype "bidirectional"))
    )
    (net (code "64") (name "unconnected-(U$4-PadNC2)") (class "Default")
      (node (ref "U$4") (pin "NC2") (pinfunction "NC2_NC2") (pintype "bidirectional"))
    )
  )
)
